# pcd.net
KiCad netlist of a schematic drawn in EAGLE
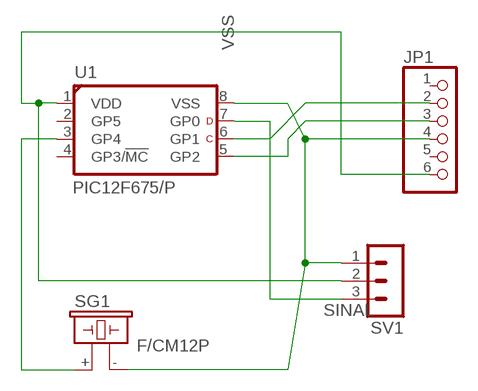
[diagram p0: schematic, sheet 1]

(export (version "E")
  (design (tool "Eeschema 10.0.6"))
  (components
    (comp (ref "JP1")
      (value "PINHD-1X6")
      (footprint "eagle-import:1X06")
      (libsource (lib "eagle-import") (part "PINHD-1X6"))
    )
    (comp (ref "SG1")
      (value "F/CM12P")
      (footprint "eagle-import:F_CM12P")
      (libsource (lib "eagle-import") (part "F/CM12P"))
    )
    (comp (ref "SV1")
      (value "MA03-1")
      (footprint "eagle-import:MA03-1")
      (libsource (lib "eagle-import") (part "MA03-1"))
    )
    (comp (ref "U1")
      (value "PIC12F675/P")
      (footprint "eagle-import:DIL8-P")
      (libsource (lib "eagle-import") (part "PIC12F675/P"))
    )
  )
  (nets
    (net (code "1") (name "/SINAL") (class "Default")
      (node (ref "SV1") (pin "3") (pinfunction "3_3") (pintype "passive"))
      (node (ref "U1") (pin "7") (pinfunction "GP0_7") (pintype "bidirectional"))
    )
    (net (code "2") (name "/VSS") (class "Default")
      (node (ref "JP1") (pin "4") (pinfunction "4_4") (pintype "passive"))
      (node (ref "SG1") (pin "-") (pinfunction "2_-") (pintype "passive"))
      (node (ref "SV1") (pin "1") (pinfunction "1_1") (pintype "passive"))
      (node (ref "U1") (pin "8") (pinfunction "VSS_8") (pintype "passive"))
    )
    (net (code "3") (name "Net-(SG1-1)") (class "Default")
      (node (ref "SG1") (pin "+") (pinfunction "1_+") (pintype "passive"))
      (node (ref "U1") (pin "3") (pinfunction "GP4_3") (pintype "bidirectional"))
    )
    (net (code "4") (name "Net-(U1-GP1)") (class "Default")
      (node (ref "JP1") (pin "2") (pinfunction "2_2") (pintype "passive"))
      (node (ref "U1") (pin "6") (pinfunction "GP1_6") (pintype "bidirectional"))
    )
    (net (code "5") (name "Net-(U1-GP2)") (class "Default")
      (node (ref "JP1") (pin "3") (pinfunction "3_3") (pintype "passive"))
      (node (ref "U1") (pin "5") (pinfunction "GP2_5") (pintype "bidirectional"))
    )
    (net (code "6") (name "Net-(U1-VDD)") (class "Default")
      (node (ref "JP1") (pin "6") (pinfunction "6_6") (pintype "passive"))
      (node (ref "SV1") (pin "2") (pinfunction "2_2") (pintype "passive"))
      (node (ref "U1") (pin "1") (pinfunction "VDD_1") (pintype "passive"))
    )
    (net (code "7") (name "unconnected-(JP1-Pad1)") (class "Default")
      (node (ref "JP1") (pin "1") (pinfunction "1_1") (pintype "passive"))
    )
    (net (code "8") (name "unconnected-(JP1-Pad5)") (class "Default")
      (node (ref "JP1") (pin "5") (pinfunction "5_5") (pintype "passive"))
    )
    (net (code "9") (name "unconnected-(U1-GP3{slash}~{MC}-Pad4)") (class "Default")
      (node (ref "U1") (pin "4") (pinfunction "GP3/~{MC}_4") (pintype "bidirectional"))
    )
    (net (code "10") (name "unconnected-(U1-GP5-Pad2)") (class "Default")
      (node (ref "U1") (pin "2") (pinfunction "GP5_2") (pintype "bidirectional"))
    )
  )
)
